# SCH_MAX7219_SHIELD.net
KiCad netlist of a schematic drawn in Altium Designer
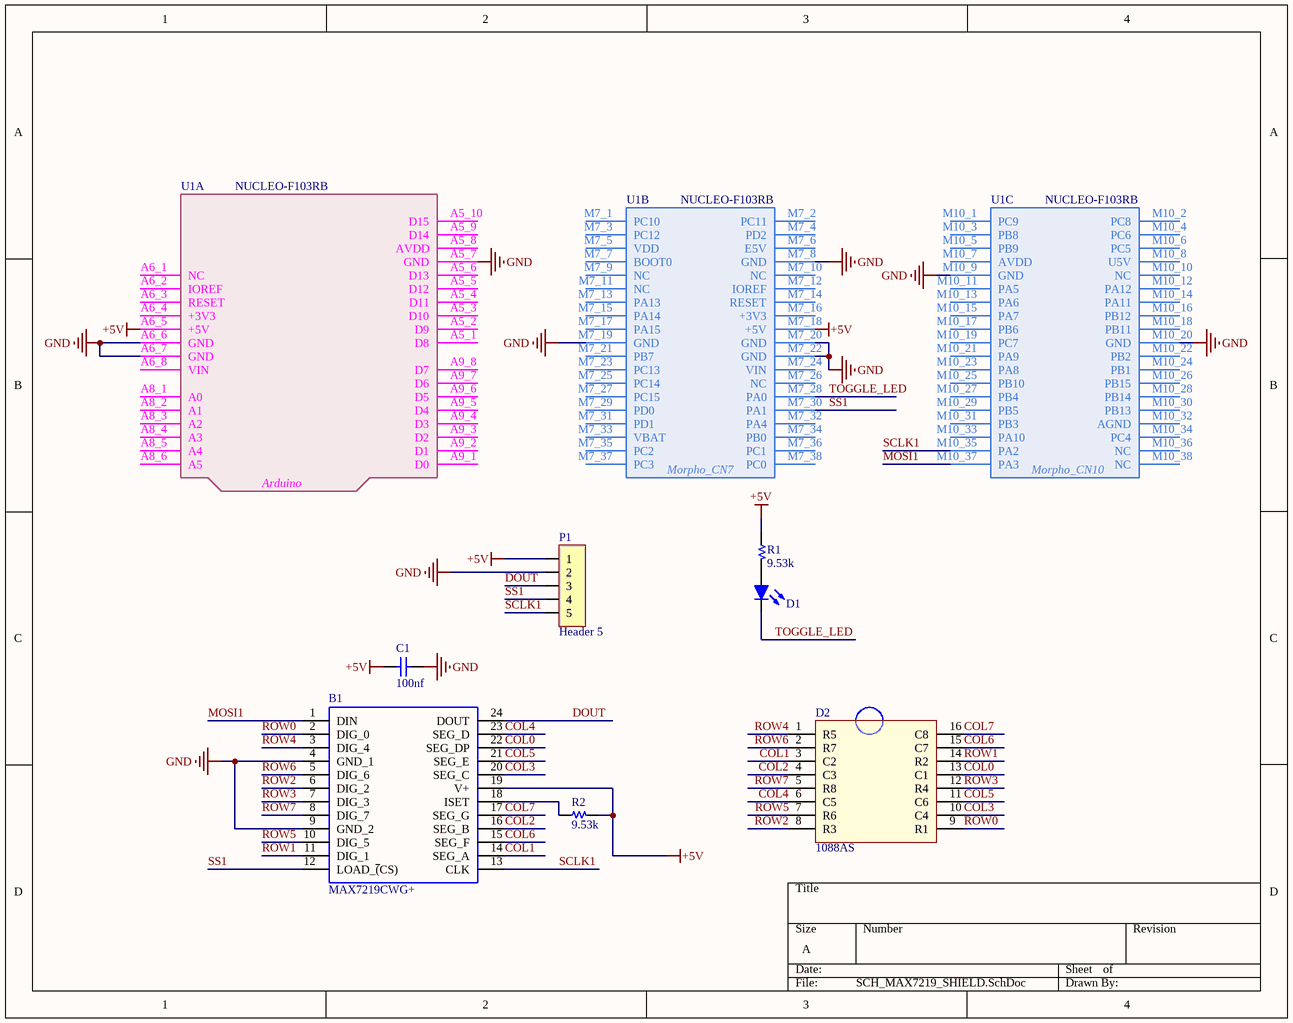
[diagram p0: SCH_MAX7219_SHIELD.SchDoc]

(export (version "E")
  (design (tool "Eeschema 10.0.6"))
  (components
    (comp (ref "B1")
      (value "MAX7219CWG+")
      (footprint "SOIC127P1032X265-24N")
      (description "MAX7219CWG+, LED Driver, 8-Digits 64-Segments, 5V, 24-Pin SOIC W")
      (fields (field (name "MOUSER PART NUMBER") "700-MAX7219CWG"))
      (libsource (lib "MAX7219CWG+") (part "MAX7219CWG+"))
    )
    (comp (ref "C1")
      (value "100nf")
      (footprint "CAP Ceramic/W300")
      (description "Capacitor non-pol")
      (libsource (lib "chipfc_libs") (part "Capacitor NP"))
    )
    (comp (ref "D1")
      (value "Led")
      (footprint "Led 0805")
      (description "Typical LED")
      (libsource (lib "led") (part "Led"))
    )
    (comp (ref "D2")
      (value "1088AS")
      (footprint "LED/MATRIX/1088")
      (description "1088AS, Common-Cathode, LED Matrix 8x8, RED, 32x32mm")
      (libsource (lib "led") (part "LED MATRIX 1088AS"))
    )
    (comp (ref "P1")
      (value "Header 5")
      (footprint "HDR/Header/5")
      (description "Header, 5-Pin")
      (libsource (lib "connectors") (part "Header 5"))
    )
    (comp (ref "R1")
      (value "9.53k")
      (footprint "R 0805")
      (description "Resistor")
      (libsource (lib "chipfc_libs") (part "Resistor"))
    )
    (comp (ref "R2")
      (value "9.53k")
      (footprint "R 0805")
      (description "Resistor")
      (libsource (lib "chipfc_libs") (part "Resistor"))
    )
    (comp (ref "U1")
      (value "NUCLEO-F103RB")
      (footprint "NUCLEO")
      (fields (field (name "MANUFACTURER") "STMicroelectronics"))
      (libsource (lib "nucleo") (part "NUCLEO-F103RB"))
    )
  )
  (nets
    (net (code "1") (name "+5V") (class "Default")
      (node (ref "B1") (pin "19") (pinfunction "V+_19") (pintype "passive"))
      (node (ref "C1") (pin "2") (pinfunction "2_2") (pintype "passive"))
      (node (ref "P1") (pin "1") (pinfunction "1_1") (pintype "passive"))
      (node (ref "R1") (pin "1") (pinfunction "1_1") (pintype "passive"))
      (node (ref "R2") (pin "2") (pinfunction "2_2") (pintype "passive"))
      (node (ref "U1") (pin "A6_5") (pinfunction "+5V_A6_5") (pintype "passive"))
      (node (ref "U1") (pin "M7_18") (pinfunction "+5V_M7_18") (pintype "passive"))
    )
    (net (code "2") (name "/COL0") (class "Default")
      (node (ref "B1") (pin "22") (pinfunction "SEG_DP_22") (pintype "passive"))
      (node (ref "D2") (pin "13") (pinfunction "C1_13") (pintype "passive"))
    )
    (net (code "3") (name "/COL1") (class "Default")
      (node (ref "B1") (pin "14") (pinfunction "SEG_A_14") (pintype "passive"))
      (node (ref "D2") (pin "3") (pinfunction "C2_3") (pintype "passive"))
    )
    (net (code "4") (name "/COL2") (class "Default")
      (node (ref "B1") (pin "16") (pinfunction "SEG_B_16") (pintype "passive"))
      (node (ref "D2") (pin "4") (pinfunction "C3_4") (pintype "passive"))
    )
    (net (code "5") (name "/COL3") (class "Default")
      (node (ref "B1") (pin "20") (pinfunction "SEG_C_20") (pintype "passive"))
      (node (ref "D2") (pin "10") (pinfunction "C4_10") (pintype "passive"))
    )
    (net (code "6") (name "/COL4") (class "Default")
      (node (ref "B1") (pin "23") (pinfunction "SEG_D_23") (pintype "passive"))
      (node (ref "D2") (pin "6") (pinfunction "C5_6") (pintype "passive"))
    )
    (net (code "7") (name "/COL5") (class "Default")
      (node (ref "B1") (pin "21") (pinfunction "SEG_E_21") (pintype "passive"))
      (node (ref "D2") (pin "11") (pinfunction "C6_11") (pintype "passive"))
    )
    (net (code "8") (name "/COL6") (class "Default")
      (node (ref "B1") (pin "15") (pinfunction "SEG_F_15") (pintype "passive"))
      (node (ref "D2") (pin "15") (pinfunction "C7_15") (pintype "passive"))
    )
    (net (code "9") (name "/COL7") (class "Default")
      (node (ref "B1") (pin "17") (pinfunction "SEG_G_17") (pintype "passive"))
      (node (ref "D2") (pin "16") (pinfunction "C8_16") (pintype "passive"))
    )
    (net (code "10") (name "/DOUT") (class "Default")
      (node (ref "B1") (pin "24") (pinfunction "DOUT_24") (pintype "passive"))
      (node (ref "P1") (pin "3") (pinfunction "3_3") (pintype "passive"))
    )
    (net (code "11") (name "/MOSI1") (class "Default")
      (node (ref "B1") (pin "1") (pinfunction "DIN_1") (pintype "passive"))
      (node (ref "U1") (pin "M10_37") (pinfunction "PA3_M10_37") (pintype "passive"))
    )
    (net (code "12") (name "/ROW0") (class "Default")
      (node (ref "B1") (pin "2") (pinfunction "DIG_0_2") (pintype "passive"))
      (node (ref "D2") (pin "9") (pinfunction "R1_9") (pintype "passive"))
    )
    (net (code "13") (name "/ROW1") (class "Default")
      (node (ref "B1") (pin "11") (pinfunction "DIG_1_11") (pintype "passive"))
      (node (ref "D2") (pin "14") (pinfunction "R2_14") (pintype "passive"))
    )
    (net (code "14") (name "/ROW2") (class "Default")
      (node (ref "B1") (pin "6") (pinfunction "DIG_2_6") (pintype "passive"))
      (node (ref "D2") (pin "8") (pinfunction "R3_8") (pintype "passive"))
    )
    (net (code "15") (name "/ROW3") (class "Default")
      (node (ref "B1") (pin "7") (pinfunction "DIG_3_7") (pintype "passive"))
      (node (ref "D2") (pin "12") (pinfunction "R4_12") (pintype "passive"))
    )
    (net (code "16") (name "/ROW4") (class "Default")
      (node (ref "B1") (pin "3") (pinfunction "DIG_4_3") (pintype "passive"))
      (node (ref "D2") (pin "1") (pinfunction "R5_1") (pintype "passive"))
    )
    (net (code "17") (name "/ROW5") (class "Default")
      (node (ref "B1") (pin "10") (pinfunction "DIG_5_10") (pintype "passive"))
      (node (ref "D2") (pin "7") (pinfunction "R6_7") (pintype "passive"))
    )
    (net (code "18") (name "/ROW6") (class "Default")
      (node (ref "B1") (pin "5") (pinfunction "DIG_6_5") (pintype "passive"))
      (node (ref "D2") (pin "2") (pinfunction "R7_2") (pintype "passive"))
    )
    (net (code "19") (name "/ROW7") (class "Default")
      (node (ref "B1") (pin "8") (pinfunction "DIG_7_8") (pintype "passive"))
      (node (ref "D2") (pin "5") (pinfunction "R8_5") (pintype "passive"))
    )
    (net (code "20") (name "/SCLK1") (class "Default")
      (node (ref "B1") (pin "13") (pinfunction "CLK_13") (pintype "passive"))
      (node (ref "P1") (pin "5") (pinfunction "5_5") (pintype "passive"))
      (node (ref "U1") (pin "M10_35") (pinfunction "PA2_M10_35") (pintype "passive"))
    )
    (net (code "21") (name "/SS1") (class "Default")
      (node (ref "B1") (pin "12") (pinfunction "LOAD_~{(}CS)_12") (pintype "passive"))
      (node (ref "P1") (pin "4") (pinfunction "4_4") (pintype "passive"))
      (node (ref "U1") (pin "M7_30") (pinfunction "PA1_M7_30") (pintype "passive"))
    )
    (net (code "22") (name "/TOGGLE_LED") (class "Default")
      (node (ref "D1") (pin "2") (pinfunction "K_2") (pintype "passive"))
      (node (ref "U1") (pin "M7_28") (pinfunction "PA0_M7_28") (pintype "passive"))
    )
    (net (code "23") (name "GND") (class "Default")
      (node (ref "B1") (pin "4") (pinfunction "GND_1_4") (pintype "passive"))
      (node (ref "B1") (pin "9") (pinfunction "GND_2_9") (pintype "passive"))
      (node (ref "C1") (pin "1") (pinfunction "1_1") (pintype "passive"))
      (node (ref "P1") (pin "2") (pinfunction "2_2") (pintype "passive"))
      (node (ref "U1") (pin "A5_7") (pinfunction "GND_A5_7") (pintype "passive"))
      (node (ref "U1") (pin "A6_6") (pinfunction "GND_A6_6") (pintype "passive"))
      (node (ref "U1") (pin "A6_7") (pinfunction "GND_A6_7") (pintype "passive"))
      (node (ref "U1") (pin "M10_20") (pinfunction "GND_M10_20") (pintype "passive"))
      (node (ref "U1") (pin "M10_9") (pinfunction "GND_M10_9") (pintype "passive"))
      (node (ref "U1") (pin "M7_19") (pinfunction "GND_M7_19") (pintype "passive"))
      (node (ref "U1") (pin "M7_20") (pinfunction "GND_M7_20") (pintype "passive"))
      (node (ref "U1") (pin "M7_22") (pinfunction "GND_M7_22") (pintype "passive"))
      (node (ref "U1") (pin "M7_8") (pinfunction "GND_M7_8") (pintype "passive"))
    )
    (net (code "24") (name "Net-(B1-ISET)") (class "Default")
      (node (ref "B1") (pin "18") (pinfunction "ISET_18") (pintype "passive"))
      (node (ref "R2") (pin "1") (pinfunction "1_1") (pintype "passive"))
    )
    (net (code "25") (name "Net-(D1-A)") (class "Default")
      (node (ref "D1") (pin "1") (pinfunction "A_1") (pintype "passive"))
      (node (ref "R1") (pin "2") (pinfunction "2_2") (pintype "passive"))
    )
    (net (code "26") (name "unconnected-(U1A-+3V3-PadA6_4)") (class "Default")
      (node (ref "U1") (pin "A6_4") (pinfunction "+3V3_A6_4") (pintype "passive"))
    )
    (net (code "27") (name "unconnected-(U1A-A0-PadA8_1)") (class "Default")
      (node (ref "U1") (pin "A8_1") (pinfunction "A0_A8_1") (pintype "passive"))
    )
    (net (code "28") (name "unconnected-(U1A-A1-PadA8_2)") (class "Default")
      (node (ref "U1") (pin "A8_2") (pinfunction "A1_A8_2") (pintype "passive"))
    )
    (net (code "29") (name "unconnected-(U1A-A2-PadA8_3)") (class "Default")
      (node (ref "U1") (pin "A8_3") (pinfunction "A2_A8_3") (pintype "passive"))
    )
    (net (code "30") (name "unconnected-(U1A-A3-PadA8_4)") (class "Default")
      (node (ref "U1") (pin "A8_4") (pinfunction "A3_A8_4") (pintype "passive"))
    )
    (net (code "31") (name "unconnected-(U1A-A4-PadA8_5)") (class "Default")
      (node (ref "U1") (pin "A8_5") (pinfunction "A4_A8_5") (pintype "passive"))
    )
    (net (code "32") (name "unconnected-(U1A-A5-PadA8_6)") (class "Default")
      (node (ref "U1") (pin "A8_6") (pinfunction "A5_A8_6") (pintype "passive"))
    )
    (net (code "33") (name "unconnected-(U1A-AVDD-PadA5_8)") (class "Default")
      (node (ref "U1") (pin "A5_8") (pinfunction "AVDD_A5_8") (pintype "passive"))
    )
    (net (code "34") (name "unconnected-(U1A-D0-PadA9_1)") (class "Default")
      (node (ref "U1") (pin "A9_1") (pinfunction "D0_A9_1") (pintype "passive"))
    )
    (net (code "35") (name "unconnected-(U1A-D1-PadA9_2)") (class "Default")
      (node (ref "U1") (pin "A9_2") (pinfunction "D1_A9_2") (pintype "passive"))
    )
    (net (code "36") (name "unconnected-(U1A-D2-PadA9_3)") (class "Default")
      (node (ref "U1") (pin "A9_3") (pinfunction "D2_A9_3") (pintype "passive"))
    )
    (net (code "37") (name "unconnected-(U1A-D3-PadA9_4)") (class "Default")
      (node (ref "U1") (pin "A9_4") (pinfunction "D3_A9_4") (pintype "passive"))
    )
    (net (code "38") (name "unconnected-(U1A-D4-PadA9_5)") (class "Default")
      (node (ref "U1") (pin "A9_5") (pinfunction "D4_A9_5") (pintype "passive"))
    )
    (net (code "39") (name "unconnected-(U1A-D5-PadA9_6)") (class "Default")
      (node (ref "U1") (pin "A9_6") (pinfunction "D5_A9_6") (pintype "passive"))
    )
    (net (code "40") (name "unconnected-(U1A-D6-PadA9_7)") (class "Default")
      (node (ref "U1") (pin "A9_7") (pinfunction "D6_A9_7") (pintype "passive"))
    )
    (net (code "41") (name "unconnected-(U1A-D7-PadA9_8)") (class "Default")
      (node (ref "U1") (pin "A9_8") (pinfunction "D7_A9_8") (pintype "passive"))
    )
    (net (code "42") (name "unconnected-(U1A-D8-PadA5_1)") (class "Default")
      (node (ref "U1") (pin "A5_1") (pinfunction "D8_A5_1") (pintype "passive"))
    )
    (net (code "43") (name "unconnected-(U1A-D9-PadA5_2)") (class "Default")
      (node (ref "U1") (pin "A5_2") (pinfunction "D9_A5_2") (pintype "passive"))
    )
    (net (code "44") (name "unconnected-(U1A-D10-PadA5_3)") (class "Default")
      (node (ref "U1") (pin "A5_3") (pinfunction "D10_A5_3") (pintype "passive"))
    )
    (net (code "45") (name "unconnected-(U1A-D11-PadA5_4)") (class "Default")
      (node (ref "U1") (pin "A5_4") (pinfunction "D11_A5_4") (pintype "passive"))
    )
    (net (code "46") (name "unconnected-(U1A-D12-PadA5_5)") (class "Default")
      (node (ref "U1") (pin "A5_5") (pinfunction "D12_A5_5") (pintype "passive"))
    )
    (net (code "47") (name "unconnected-(U1A-D13-PadA5_6)") (class "Default")
      (node (ref "U1") (pin "A5_6") (pinfunction "D13_A5_6") (pintype "passive"))
    )
    (net (code "48") (name "unconnected-(U1A-D14-PadA5_9)") (class "Default")
      (node (ref "U1") (pin "A5_9") (pinfunction "D14_A5_9") (pintype "passive"))
    )
    (net (code "49") (name "unconnected-(U1A-D15-PadA5_10)") (class "Default")
      (node (ref "U1") (pin "A5_10") (pinfunction "D15_A5_10") (pintype "passive"))
    )
    (net (code "50") (name "unconnected-(U1A-IOREF-PadA6_2)") (class "Default")
      (node (ref "U1") (pin "A6_2") (pinfunction "IOREF_A6_2") (pintype "passive"))
    )
    (net (code "51") (name "unconnected-(U1A-NC-PadA6_1)") (class "Default")
      (node (ref "U1") (pin "A6_1") (pinfunction "NC_A6_1") (pintype "passive"))
    )
    (net (code "52") (name "unconnected-(U1A-RESET-PadA6_3)") (class "Default")
      (node (ref "U1") (pin "A6_3") (pinfunction "RESET_A6_3") (pintype "passive"))
    )
    (net (code "53") (name "unconnected-(U1A-VIN-PadA6_8)") (class "Default")
      (node (ref "U1") (pin "A6_8") (pinfunction "VIN_A6_8") (pintype "passive"))
    )
    (net (code "54") (name "unconnected-(U1B-+3V3-PadM7_16)") (class "Default")
      (node (ref "U1") (pin "M7_16") (pinfunction "+3V3_M7_16") (pintype "passive"))
    )
    (net (code "55") (name "unconnected-(U1B-BOOT0-PadM7_7)") (class "Default")
      (node (ref "U1") (pin "M7_7") (pinfunction "BOOT0_M7_7") (pintype "passive"))
    )
    (net (code "56") (name "unconnected-(U1B-E5V-PadM7_6)") (class "Default")
      (node (ref "U1") (pin "M7_6") (pinfunction "E5V_M7_6") (pintype "passive"))
    )
    (net (code "57") (name "unconnected-(U1B-IOREF-PadM7_12)") (class "Default")
      (node (ref "U1") (pin "M7_12") (pinfunction "IOREF_M7_12") (pintype "passive"))
    )
    (net (code "58") (name "unconnected-(U1B-NC-PadM7_9)") (class "Default")
      (node (ref "U1") (pin "M7_9") (pinfunction "NC_M7_9") (pintype "passive"))
    )
    (net (code "59") (name "unconnected-(U1B-NC-PadM7_10)") (class "Default")
      (node (ref "U1") (pin "M7_10") (pinfunction "NC_M7_10") (pintype "passive"))
    )
    (net (code "60") (name "unconnected-(U1B-NC-PadM7_11)") (class "Default")
      (node (ref "U1") (pin "M7_11") (pinfunction "NC_M7_11") (pintype "passive"))
    )
    (net (code "61") (name "unconnected-(U1B-NC-PadM7_26)") (class "Default")
      (node (ref "U1") (pin "M7_26") (pinfunction "NC_M7_26") (pintype "passive"))
    )
    (net (code "62") (name "unconnected-(U1B-PA4-PadM7_32)") (class "Default")
      (node (ref "U1") (pin "M7_32") (pinfunction "PA4_M7_32") (pintype "passive"))
    )
    (net (code "63") (name "unconnected-(U1B-PA13-PadM7_13)") (class "Default")
      (node (ref "U1") (pin "M7_13") (pinfunction "PA13_M7_13") (pintype "passive"))
    )
    (net (code "64") (name "unconnected-(U1B-PA14-PadM7_15)") (class "Default")
      (node (ref "U1") (pin "M7_15") (pinfunction "PA14_M7_15") (pintype "passive"))
    )
    (net (code "65") (name "unconnected-(U1B-PA15-PadM7_17)") (class "Default")
      (node (ref "U1") (pin "M7_17") (pinfunction "PA15_M7_17") (pintype "passive"))
    )
    (net (code "66") (name "unconnected-(U1B-PB0-PadM7_34)") (class "Default")
      (node (ref "U1") (pin "M7_34") (pinfunction "PB0_M7_34") (pintype "passive"))
    )
    (net (code "67") (name "unconnected-(U1B-PB7-PadM7_21)") (class "Default")
      (node (ref "U1") (pin "M7_21") (pinfunction "PB7_M7_21") (pintype "passive"))
    )
    (net (code "68") (name "unconnected-(U1B-PC0-PadM7_38)") (class "Default")
      (node (ref "U1") (pin "M7_38") (pinfunction "PC0_M7_38") (pintype "passive"))
    )
    (net (code "69") (name "unconnected-(U1B-PC1-PadM7_36)") (class "Default")
      (node (ref "U1") (pin "M7_36") (pinfunction "PC1_M7_36") (pintype "passive"))
    )
    (net (code "70") (name "unconnected-(U1B-PC2-PadM7_35)") (class "Default")
      (node (ref "U1") (pin "M7_35") (pinfunction "PC2_M7_35") (pintype "passive"))
    )
    (net (code "71") (name "unconnected-(U1B-PC3-PadM7_37)") (class "Default")
      (node (ref "U1") (pin "M7_37") (pinfunction "PC3_M7_37") (pintype "passive"))
    )
    (net (code "72") (name "unconnected-(U1B-PC10-PadM7_1)") (class "Default")
      (node (ref "U1") (pin "M7_1") (pinfunction "PC10_M7_1") (pintype "passive"))
    )
    (net (code "73") (name "unconnected-(U1B-PC11-PadM7_2)") (class "Default")
      (node (ref "U1") (pin "M7_2") (pinfunction "PC11_M7_2") (pintype "passive"))
    )
    (net (code "74") (name "unconnected-(U1B-PC12-PadM7_3)") (class "Default")
      (node (ref "U1") (pin "M7_3") (pinfunction "PC12_M7_3") (pintype "passive"))
    )
    (net (code "75") (name "unconnected-(U1B-PC13-PadM7_23)") (class "Default")
      (node (ref "U1") (pin "M7_23") (pinfunction "PC13_M7_23") (pintype "passive"))
    )
    (net (code "76") (name "unconnected-(U1B-PC14-PadM7_25)") (class "Default")
      (node (ref "U1") (pin "M7_25") (pinfunction "PC14_M7_25") (pintype "passive"))
    )
    (net (code "77") (name "unconnected-(U1B-PC15-PadM7_27)") (class "Default")
      (node (ref "U1") (pin "M7_27") (pinfunction "PC15_M7_27") (pintype "passive"))
    )
    (net (code "78") (name "unconnected-(U1B-PD0-PadM7_29)") (class "Default")
      (node (ref "U1") (pin "M7_29") (pinfunction "PD0_M7_29") (pintype "passive"))
    )
    (net (code "79") (name "unconnected-(U1B-PD1-PadM7_31)") (class "Default")
      (node (ref "U1") (pin "M7_31") (pinfunction "PD1_M7_31") (pintype "passive"))
    )
    (net (code "80") (name "unconnected-(U1B-PD2-PadM7_4)") (class "Default")
      (node (ref "U1") (pin "M7_4") (pinfunction "PD2_M7_4") (pintype "passive"))
    )
    (net (code "81") (name "unconnected-(U1B-RESET-PadM7_14)") (class "Default")
      (node (ref "U1") (pin "M7_14") (pinfunction "RESET_M7_14") (pintype "passive"))
    )
    (net (code "82") (name "unconnected-(U1B-VBAT-PadM7_33)") (class "Default")
      (node (ref "U1") (pin "M7_33") (pinfunction "VBAT_M7_33") (pintype "passive"))
    )
    (net (code "83") (name "unconnected-(U1B-VDD-PadM7_5)") (class "Default")
      (node (ref "U1") (pin "M7_5") (pinfunction "VDD_M7_5") (pintype "passive"))
    )
    (net (code "84") (name "unconnected-(U1B-VIN-PadM7_24)") (class "Default")
      (node (ref "U1") (pin "M7_24") (pinfunction "VIN_M7_24") (pintype "passive"))
    )
    (net (code "85") (name "unconnected-(U1C-AGND-PadM10_32)") (class "Default")
      (node (ref "U1") (pin "M10_32") (pinfunction "AGND_M10_32") (pintype "passive"))
    )
    (net (code "86") (name "unconnected-(U1C-AVDD-PadM10_7)") (class "Default")
      (node (ref "U1") (pin "M10_7") (pinfunction "AVDD_M10_7") (pintype "passive"))
    )
    (net (code "87") (name "unconnected-(U1C-NC-PadM10_10)") (class "Default")
      (node (ref "U1") (pin "M10_10") (pinfunction "NC_M10_10") (pintype "passive"))
    )
    (net (code "88") (name "unconnected-(U1C-NC-PadM10_36)") (class "Default")
      (node (ref "U1") (pin "M10_36") (pinfunction "NC_M10_36") (pintype "passive"))
    )
    (net (code "89") (name "unconnected-(U1C-NC-PadM10_38)") (class "Default")
      (node (ref "U1") (pin "M10_38") (pinfunction "NC_M10_38") (pintype "passive"))
    )
    (net (code "90") (name "unconnected-(U1C-PA5-PadM10_11)") (class "Default")
      (node (ref "U1") (pin "M10_11") (pinfunction "PA5_M10_11") (pintype "passive"))
    )
    (net (code "91") (name "unconnected-(U1C-PA6-PadM10_13)") (class "Default")
      (node (ref "U1") (pin "M10_13") (pinfunction "PA6_M10_13") (pintype "passive"))
    )
    (net (code "92") (name "unconnected-(U1C-PA7-PadM10_15)") (class "Default")
      (node (ref "U1") (pin "M10_15") (pinfunction "PA7_M10_15") (pintype "passive"))
    )
    (net (code "93") (name "unconnected-(U1C-PA8-PadM10_23)") (class "Default")
      (node (ref "U1") (pin "M10_23") (pinfunction "PA8_M10_23") (pintype "passive"))
    )
    (net (code "94") (name "unconnected-(U1C-PA9-PadM10_21)") (class "Default")
      (node (ref "U1") (pin "M10_21") (pinfunction "PA9_M10_21") (pintype "passive"))
    )
    (net (code "95") (name "unconnected-(U1C-PA10-PadM10_33)") (class "Default")
      (node (ref "U1") (pin "M10_33") (pinfunction "PA10_M10_33") (pintype "passive"))
    )
    (net (code "96") (name "unconnected-(U1C-PA11-PadM10_14)") (class "Default")
      (node (ref "U1") (pin "M10_14") (pinfunction "PA11_M10_14") (pintype "passive"))
    )
    (net (code "97") (name "unconnected-(U1C-PA12-PadM10_12)") (class "Default")
      (node (ref "U1") (pin "M10_12") (pinfunction "PA12_M10_12") (pintype "passive"))
    )
    (net (code "98") (name "unconnected-(U1C-PB1-PadM10_24)") (class "Default")
      (node (ref "U1") (pin "M10_24") (pinfunction "PB1_M10_24") (pintype "passive"))
    )
    (net (code "99") (name "unconnected-(U1C-PB2-PadM10_22)") (class "Default")
      (node (ref "U1") (pin "M10_22") (pinfunction "PB2_M10_22") (pintype "passive"))
    )
    (net (code "100") (name "unconnected-(U1C-PB3-PadM10_31)") (class "Default")
      (node (ref "U1") (pin "M10_31") (pinfunction "PB3_M10_31") (pintype "passive"))
    )
    (net (code "101") (name "unconnected-(U1C-PB4-PadM10_27)") (class "Default")
      (node (ref "U1") (pin "M10_27") (pinfunction "PB4_M10_27") (pintype "passive"))
    )
    (net (code "102") (name "unconnected-(U1C-PB5-PadM10_29)") (class "Default")
      (node (ref "U1") (pin "M10_29") (pinfunction "PB5_M10_29") (pintype "passive"))
    )
    (net (code "103") (name "unconnected-(U1C-PB6-PadM10_17)") (class "Default")
      (node (ref "U1") (pin "M10_17") (pinfunction "PB6_M10_17") (pintype "passive"))
    )
    (net (code "104") (name "unconnected-(U1C-PB8-PadM10_3)") (class "Default")
      (node (ref "U1") (pin "M10_3") (pinfunction "PB8_M10_3") (pintype "passive"))
    )
    (net (code "105") (name "unconnected-(U1C-PB9-PadM10_5)") (class "Default")
      (node (ref "U1") (pin "M10_5") (pinfunction "PB9_M10_5") (pintype "passive"))
    )
    (net (code "106") (name "unconnected-(U1C-PB10-PadM10_25)") (class "Default")
      (node (ref "U1") (pin "M10_25") (pinfunction "PB10_M10_25") (pintype "passive"))
    )
    (net (code "107") (name "unconnected-(U1C-PB11-PadM10_18)") (class "Default")
      (node (ref "U1") (pin "M10_18") (pinfunction "PB11_M10_18") (pintype "passive"))
    )
    (net (code "108") (name "unconnected-(U1C-PB12-PadM10_16)") (class "Default")
      (node (ref "U1") (pin "M10_16") (pinfunction "PB12_M10_16") (pintype "passive"))
    )
    (net (code "109") (name "unconnected-(U1C-PB13-PadM10_30)") (class "Default")
      (node (ref "U1") (pin "M10_30") (pinfunction "PB13_M10_30") (pintype "passive"))
    )
    (net (code "110") (name "unconnected-(U1C-PB14-PadM10_28)") (class "Default")
      (node (ref "U1") (pin "M10_28") (pinfunction "PB14_M10_28") (pintype "passive"))
    )
    (net (code "111") (name "unconnected-(U1C-PB15-PadM10_26)") (class "Default")
      (node (ref "U1") (pin "M10_26") (pinfunction "PB15_M10_26") (pintype "passive"))
    )
    (net (code "112") (name "unconnected-(U1C-PC4-PadM10_34)") (class "Default")
      (node (ref "U1") (pin "M10_34") (pinfunction "PC4_M10_34") (pintype "passive"))
    )
    (net (code "113") (name "unconnected-(U1C-PC5-PadM10_6)") (class "Default")
      (node (ref "U1") (pin "M10_6") (pinfunction "PC5_M10_6") (pintype "passive"))
    )
    (net (code "114") (name "unconnected-(U1C-PC6-PadM10_4)") (class "Default")
      (node (ref "U1") (pin "M10_4") (pinfunction "PC6_M10_4") (pintype "passive"))
    )
    (net (code "115") (name "unconnected-(U1C-PC7-PadM10_19)") (class "Default")
      (node (ref "U1") (pin "M10_19") (pinfunction "PC7_M10_19") (pintype "passive"))
    )
    (net (code "116") (name "unconnected-(U1C-PC8-PadM10_2)") (class "Default")
      (node (ref "U1") (pin "M10_2") (pinfunction "PC8_M10_2") (pintype "passive"))
    )
    (net (code "117") (name "unconnected-(U1C-PC9-PadM10_1)") (class "Default")
      (node (ref "U1") (pin "M10_1") (pinfunction "PC9_M10_1") (pintype "passive"))
    )
    (net (code "118") (name "unconnected-(U1C-U5V-PadM10_8)") (class "Default")
      (node (ref "U1") (pin "M10_8") (pinfunction "U5V_M10_8") (pintype "passive"))
    )
  )
)
